# FPGA_IO.net
KiCad netlist of a schematic drawn in Altium Designer
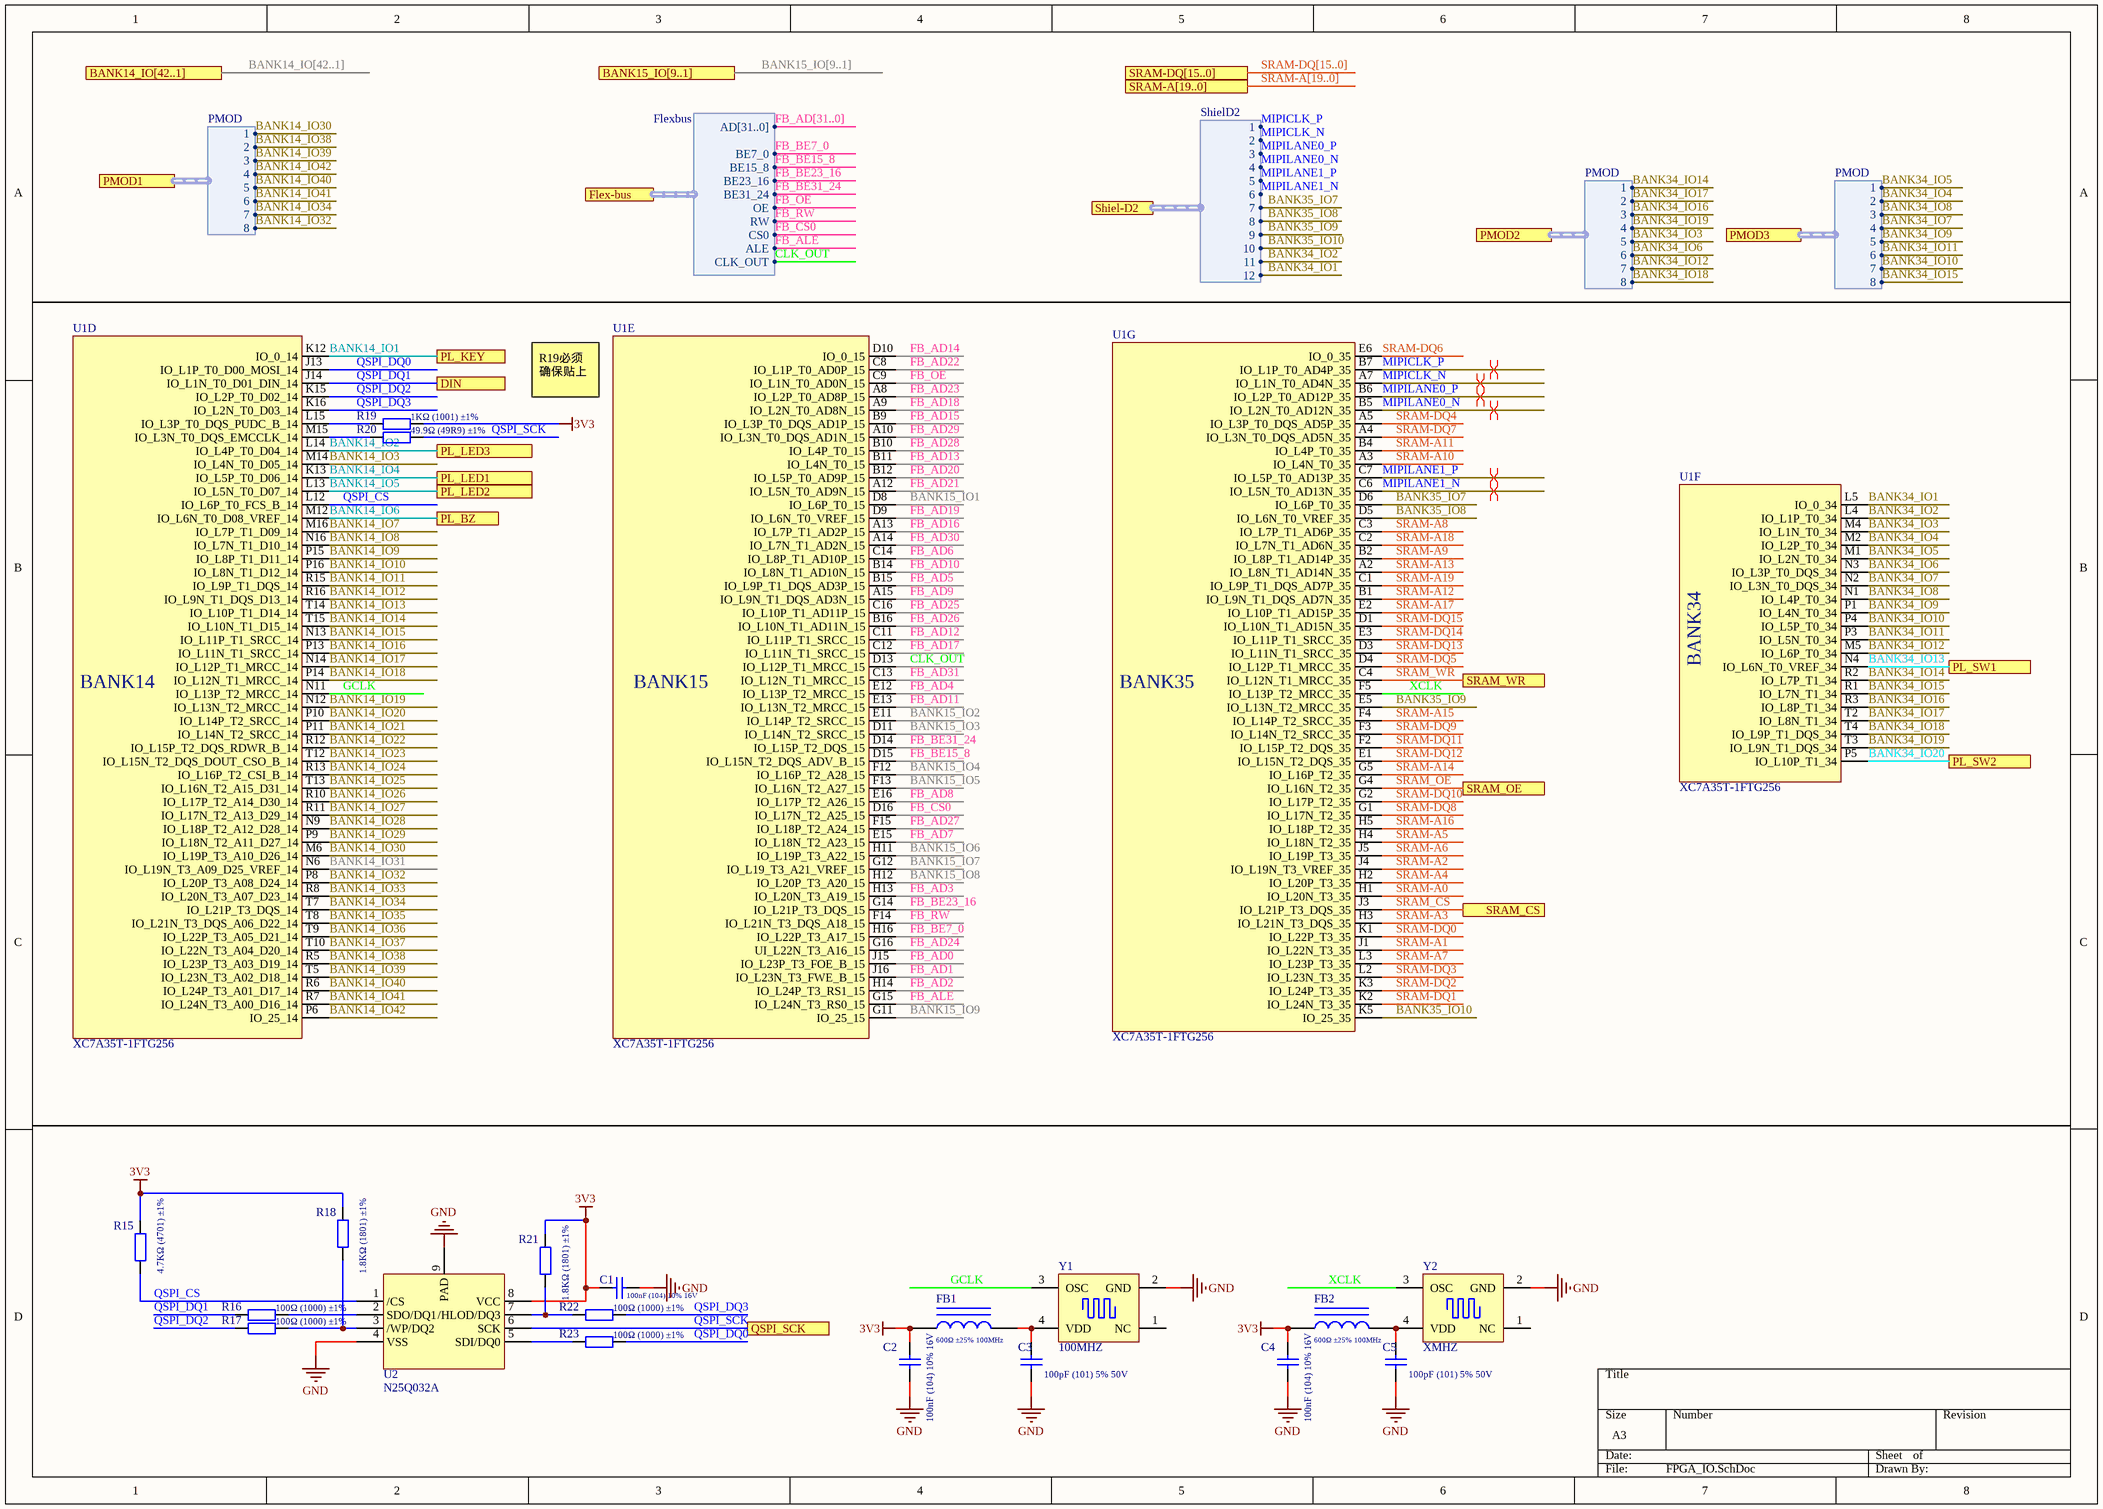
[diagram p0: FPGA_IO.SchDoc]

(export (version "E")
  (design (tool "Eeschema 10.0.6"))
  (components
    (comp (ref "C1")
      (value "100nF (104) 10% 16V")
      (footprint "0402_C")
      (description "贴片电容")
      (libsource (lib "Cap") (part "0402 100nF (104) 10% 16V"))
    )
    (comp (ref "C2")
      (value "100nF (104) 10% 16V")
      (footprint "0402_C")
      (description "贴片电容")
      (libsource (lib "Cap") (part "0402 100nF (104) 10% 16V"))
    )
    (comp (ref "C3")
      (value "100pF (101) 5% 50V")
      (footprint "0402_C")
      (description "贴片电容")
      (libsource (lib "Cap") (part "0402 100pF (101) 5% 50V"))
    )
    (comp (ref "C4")
      (value "100nF (104) 10% 16V")
      (footprint "0402_C")
      (description "贴片电容")
      (libsource (lib "Cap") (part "0402 100nF (104) 10% 16V"))
    )
    (comp (ref "C5")
      (value "100pF (101) 5% 50V")
      (footprint "0402_C")
      (description "贴片电容")
      (libsource (lib "Cap") (part "0402 100pF (101) 5% 50V"))
    )
    (comp (ref "FB1")
      (value "600Ω ±25% 100MHz")
      (footprint "0805_L")
      (description "贴片磁珠")
      (libsource (lib "IUD") (part "0805 600Ω 25% 100MHz"))
    )
    (comp (ref "FB2")
      (value "600Ω ±25% 100MHz")
      (footprint "0805_L")
      (description "贴片磁珠")
      (libsource (lib "IUD") (part "0805 600Ω 25% 100MHz"))
    )
    (comp (ref "R15")
      (value "4.7KΩ (4701) ±1%")
      (footprint "0402_R")
      (description "贴片电阻")
      (libsource (lib "RES") (part "0402 4.7KΩ (4701) 1%"))
    )
    (comp (ref "R16")
      (value "100Ω (1000) ±1%")
      (footprint "0402_R")
      (description "贴片电阻")
      (libsource (lib "RES") (part "0402 100Ω (1000) 1%"))
    )
    (comp (ref "R17")
      (value "100Ω (1000) ±1%")
      (footprint "0402_R")
      (description "贴片电阻")
      (libsource (lib "RES") (part "0402 100Ω (1000) 1%"))
    )
    (comp (ref "R18")
      (value "1.8KΩ (1801) ±1%")
      (footprint "0603_R")
      (description "贴片电阻")
      (libsource (lib "RES") (part "0603 1.8KΩ (1801) 1%"))
    )
    (comp (ref "R19")
      (value "1KΩ (1001) ±1%")
      (footprint "0402_R")
      (description "贴片电阻")
      (libsource (lib "RES") (part "0402 1KΩ (1001) 1%"))
    )
    (comp (ref "R20")
      (value "49.9Ω (49R9) ±1%")
      (footprint "0402_R")
      (description "贴片电阻")
      (libsource (lib "RES") (part "0402 49.9Ω (49R9) 1%"))
    )
    (comp (ref "R21")
      (value "1.8KΩ (1801) ±1%")
      (footprint "0603_R")
      (description "贴片电阻")
      (libsource (lib "RES") (part "0603 1.8KΩ (1801) 1%"))
    )
    (comp (ref "R22")
      (value "100Ω (1000) ±1%")
      (footprint "0402_R")
      (description "贴片电阻")
      (libsource (lib "RES") (part "0402 100Ω (1000) 1%"))
    )
    (comp (ref "R23")
      (value "100Ω (1000) ±1%")
      (footprint "0402_R")
      (description "贴片电阻")
      (libsource (lib "RES") (part "0402 100Ω (1000) 1%"))
    )
    (comp (ref "U1")
      (value "XC7A35T-1FTG256")
      (footprint "BGA100P9X9-81A")
      (libsource (lib "Schlib") (part "XC7A35T-1FTG256"))
    )
    (comp (ref "U2")
      (value "N25Q032A")
      (footprint "QFN127P500X600X100_HS-9N")
      (libsource (lib "2号库") (part "N25Q032A"))
    )
    (comp (ref "Y1") (value "100MHZ") (footprint "XTAL7_3225") (libsource (lib "K60-V4.0") (part "XTAL1")))
    (comp (ref "Y2") (value "XMHZ") (footprint "XTAL7_3225") (libsource (lib "K60-V4.0") (part "XTAL1")))
  )
  (nets
    (net (code "4") (name "/BANK14_IO1") (class "Default")
      (node (ref "U1") (pin "K12") (pinfunction "IO_0_14_K12") (pintype "passive"))
    )
    (net (code "5") (name "/BANK14_IO2") (class "Default")
      (node (ref "U1") (pin "L14") (pinfunction "IO_L4P_T0_D04_14_L14") (pintype "passive"))
    )
    (net (code "6") (name "/BANK14_IO3") (class "Default")
      (node (ref "U1") (pin "M14") (pinfunction "IO_L4N_T0_D05_14_M14") (pintype "passive"))
    )
    (net (code "7") (name "/BANK14_IO4") (class "Default")
      (node (ref "U1") (pin "K13") (pinfunction "IO_L5P_T0_D06_14_K13") (pintype "passive"))
    )
    (net (code "8") (name "/BANK14_IO5") (class "Default")
      (node (ref "U1") (pin "L13") (pinfunction "IO_L5N_T0_D07_14_L13") (pintype "passive"))
    )
    (net (code "9") (name "/BANK14_IO6") (class "Default")
      (node (ref "U1") (pin "M12") (pinfunction "IO_L6N_T0_D08_VREF_14_M12") (pintype "passive"))
    )
    (net (code "10") (name "/BANK14_IO7") (class "Default")
      (node (ref "U1") (pin "M16") (pinfunction "IO_L7P_T1_D09_14_M16") (pintype "passive"))
    )
    (net (code "11") (name "/BANK14_IO8") (class "Default")
      (node (ref "U1") (pin "N16") (pinfunction "IO_L7N_T1_D10_14_N16") (pintype "passive"))
    )
    (net (code "12") (name "/BANK14_IO9") (class "Default")
      (node (ref "U1") (pin "P15") (pinfunction "IO_L8P_T1_D11_14_P15") (pintype "passive"))
    )
    (net (code "13") (name "/BANK14_IO10") (class "Default")
      (node (ref "U1") (pin "P16") (pinfunction "IO_L8N_T1_D12_14_P16") (pintype "passive"))
    )
    (net (code "14") (name "/BANK14_IO11") (class "Default")
      (node (ref "U1") (pin "R15") (pinfunction "IO_L9P_T1_DQS_14_R15") (pintype "passive"))
    )
    (net (code "15") (name "/BANK14_IO12") (class "Default")
      (node (ref "U1") (pin "R16") (pinfunction "IO_L9N_T1_DQS_D13_14_R16") (pintype "passive"))
    )
    (net (code "16") (name "/BANK14_IO13") (class "Default")
      (node (ref "U1") (pin "T14") (pinfunction "IO_L10P_T1_D14_14_T14") (pintype "passive"))
    )
    (net (code "17") (name "/BANK14_IO14") (class "Default")
      (node (ref "U1") (pin "T15") (pinfunction "IO_L10N_T1_D15_14_T15") (pintype "passive"))
    )
    (net (code "18") (name "/BANK14_IO15") (class "Default")
      (node (ref "U1") (pin "N13") (pinfunction "IO_L11P_T1_SRCC_14_N13") (pintype "passive"))
    )
    (net (code "19") (name "/BANK14_IO16") (class "Default")
      (node (ref "U1") (pin "P13") (pinfunction "IO_L11N_T1_SRCC_14_P13") (pintype "passive"))
    )
    (net (code "20") (name "/BANK14_IO17") (class "Default")
      (node (ref "U1") (pin "N14") (pinfunction "IO_L12P_T1_MRCC_14_N14") (pintype "passive"))
    )
    (net (code "21") (name "/BANK14_IO18") (class "Default")
      (node (ref "U1") (pin "P14") (pinfunction "IO_L12N_T1_MRCC_14_P14") (pintype "passive"))
    )
    (net (code "22") (name "/BANK14_IO19") (class "Default")
      (node (ref "U1") (pin "N12") (pinfunction "IO_L13N_T2_MRCC_14_N12") (pintype "passive"))
    )
    (net (code "23") (name "/BANK14_IO20") (class "Default")
      (node (ref "U1") (pin "P10") (pinfunction "IO_L14P_T2_SRCC_14_P10") (pintype "passive"))
    )
    (net (code "24") (name "/BANK14_IO21") (class "Default")
      (node (ref "U1") (pin "P11") (pinfunction "IO_L14N_T2_SRCC_14_P11") (pintype "passive"))
    )
    (net (code "25") (name "/BANK14_IO22") (class "Default")
      (node (ref "U1") (pin "R12") (pinfunction "IO_L15P_T2_DQS_RDWR_B_14_R12") (pintype "passive"))
    )
    (net (code "26") (name "/BANK14_IO23") (class "Default")
      (node (ref "U1") (pin "T12") (pinfunction "IO_L15N_T2_DQS_DOUT_CSO_B_14_T12") (pintype "passive"))
    )
    (net (code "27") (name "/BANK14_IO24") (class "Default")
      (node (ref "U1") (pin "R13") (pinfunction "IO_L16P_T2_CSI_B_14_R13") (pintype "passive"))
    )
    (net (code "28") (name "/BANK14_IO25") (class "Default")
      (node (ref "U1") (pin "T13") (pinfunction "IO_L16N_T2_A15_D31_14_T13") (pintype "passive"))
    )
    (net (code "29") (name "/BANK14_IO26") (class "Default")
      (node (ref "U1") (pin "R10") (pinfunction "IO_L17P_T2_A14_D30_14_R10") (pintype "passive"))
    )
    (net (code "30") (name "/BANK14_IO27") (class "Default")
      (node (ref "U1") (pin "R11") (pinfunction "IO_L17N_T2_A13_D29_14_R11") (pintype "passive"))
    )
    (net (code "31") (name "/BANK14_IO28") (class "Default")
      (node (ref "U1") (pin "N9") (pinfunction "IO_L18P_T2_A12_D28_14_N9") (pintype "passive"))
    )
    (net (code "32") (name "/BANK14_IO29") (class "Default")
      (node (ref "U1") (pin "P9") (pinfunction "IO_L18N_T2_A11_D27_14_P9") (pintype "passive"))
    )
    (net (code "33") (name "/BANK14_IO30") (class "Default")
      (node (ref "U1") (pin "M6") (pinfunction "IO_L19P_T3_A10_D26_14_M6") (pintype "passive"))
    )
    (net (code "34") (name "/BANK14_IO31") (class "Default")
      (node (ref "U1") (pin "N6") (pinfunction "IO_L19N_T3_A09_D25_VREF_14_N6") (pintype "passive"))
    )
    (net (code "35") (name "/BANK14_IO32") (class "Default")
      (node (ref "U1") (pin "P8") (pinfunction "IO_L20P_T3_A08_D24_14_P8") (pintype "passive"))
    )
    (net (code "36") (name "/BANK14_IO33") (class "Default")
      (node (ref "U1") (pin "R8") (pinfunction "IO_L20N_T3_A07_D23_14_R8") (pintype "passive"))
    )
    (net (code "37") (name "/BANK14_IO34") (class "Default")
      (node (ref "U1") (pin "T7") (pinfunction "IO_L21P_T3_DQS_14_T7") (pintype "passive"))
    )
    (net (code "38") (name "/BANK14_IO35") (class "Default")
      (node (ref "U1") (pin "T8") (pinfunction "IO_L21N_T3_DQS_A06_D22_14_T8") (pintype "passive"))
    )
    (net (code "39") (name "/BANK14_IO36") (class "Default")
      (node (ref "U1") (pin "T9") (pinfunction "IO_L22P_T3_A05_D21_14_T9") (pintype "passive"))
    )
    (net (code "40") (name "/BANK14_IO37") (class "Default")
      (node (ref "U1") (pin "T10") (pinfunction "IO_L22N_T3_A04_D20_14_T10") (pintype "passive"))
    )
    (net (code "41") (name "/BANK14_IO38") (class "Default")
      (node (ref "U1") (pin "R5") (pinfunction "IO_L23P_T3_A03_D19_14_R5") (pintype "passive"))
    )
    (net (code "42") (name "/BANK14_IO39") (class "Default")
      (node (ref "U1") (pin "T5") (pinfunction "IO_L23N_T3_A02_D18_14_T5") (pintype "passive"))
    )
    (net (code "43") (name "/BANK14_IO40") (class "Default")
      (node (ref "U1") (pin "R6") (pinfunction "IO_L24P_T3_A01_D17_14_R6") (pintype "passive"))
    )
    (net (code "44") (name "/BANK14_IO41") (class "Default")
      (node (ref "U1") (pin "R7") (pinfunction "IO_L24N_T3_A00_D16_14_R7") (pintype "passive"))
    )
    (net (code "45") (name "/BANK14_IO42") (class "Default")
      (node (ref "U1") (pin "P6") (pinfunction "IO_25_14_P6") (pintype "passive"))
    )
    (net (code "47") (name "/BANK15_IO1") (class "Default")
      (node (ref "U1") (pin "D8") (pinfunction "IO_L6P_T0_15_D8") (pintype "passive"))
    )
    (net (code "48") (name "/BANK15_IO2") (class "Default")
      (node (ref "U1") (pin "E11") (pinfunction "IO_L14P_T2_SRCC_15_E11") (pintype "passive"))
    )
    (net (code "49") (name "/BANK15_IO3") (class "Default")
      (node (ref "U1") (pin "D11") (pinfunction "IO_L14N_T2_SRCC_15_D11") (pintype "passive"))
    )
    (net (code "50") (name "/BANK15_IO4") (class "Default")
      (node (ref "U1") (pin "F12") (pinfunction "IO_L16P_T2_A28_15_F12") (pintype "passive"))
    )
    (net (code "51") (name "/BANK15_IO5") (class "Default")
      (node (ref "U1") (pin "F13") (pinfunction "IO_L16N_T2_A27_15_F13") (pintype "passive"))
    )
    (net (code "52") (name "/BANK15_IO6") (class "Default")
      (node (ref "U1") (pin "H11") (pinfunction "IO_L19P_T3_A22_15_H11") (pintype "passive"))
    )
    (net (code "53") (name "/BANK15_IO7") (class "Default")
      (node (ref "U1") (pin "G12") (pinfunction "IO_L19_T3_A21_VREF_15_G12") (pintype "passive"))
    )
    (net (code "54") (name "/BANK15_IO8") (class "Default")
      (node (ref "U1") (pin "H12") (pinfunction "IO_L20P_T3_A20_15_H12") (pintype "passive"))
    )
    (net (code "55") (name "/BANK15_IO9") (class "Default")
      (node (ref "U1") (pin "G11") (pinfunction "IO_25_15_G11") (pintype "passive"))
    )
    (net (code "57") (name "/BANK34_IO1") (class "Default")
      (node (ref "U1") (pin "L5") (pinfunction "IO_0_34_L5") (pintype "passive"))
    )
    (net (code "58") (name "/BANK34_IO2") (class "Default")
      (node (ref "U1") (pin "L4") (pinfunction "IO_L1P_T0_34_L4") (pintype "passive"))
    )
    (net (code "59") (name "/BANK34_IO3") (class "Default")
      (node (ref "U1") (pin "M4") (pinfunction "IO_L1N_T0_34_M4") (pintype "passive"))
    )
    (net (code "60") (name "/BANK34_IO4") (class "Default")
      (node (ref "U1") (pin "M2") (pinfunction "IO_L2P_T0_34_M2") (pintype "passive"))
    )
    (net (code "61") (name "/BANK34_IO5") (class "Default")
      (node (ref "U1") (pin "M1") (pinfunction "IO_L2N_T0_34_M1") (pintype "passive"))
    )
    (net (code "62") (name "/BANK34_IO6") (class "Default")
      (node (ref "U1") (pin "N3") (pinfunction "IO_L3P_T0_DQS_34_N3") (pintype "passive"))
    )
    (net (code "63") (name "/BANK34_IO7") (class "Default")
      (node (ref "U1") (pin "N2") (pinfunction "IO_L3N_T0_DQS_34_N2") (pintype "passive"))
    )
    (net (code "64") (name "/BANK34_IO8") (class "Default")
      (node (ref "U1") (pin "N1") (pinfunction "IO_L4P_T0_34_N1") (pintype "passive"))
    )
    (net (code "65") (name "/BANK34_IO9") (class "Default")
      (node (ref "U1") (pin "P1") (pinfunction "IO_L4N_T0_34_P1") (pintype "passive"))
    )
    (net (code "66") (name "/BANK34_IO10") (class "Default")
      (node (ref "U1") (pin "P4") (pinfunction "IO_L5P_T0_34_P4") (pintype "passive"))
    )
    (net (code "67") (name "/BANK34_IO11") (class "Default")
      (node (ref "U1") (pin "P3") (pinfunction "IO_L5N_T0_34_P3") (pintype "passive"))
    )
    (net (code "68") (name "/BANK34_IO12") (class "Default")
      (node (ref "U1") (pin "M5") (pinfunction "IO_L6P_T0_34_M5") (pintype "passive"))
    )
    (net (code "69") (name "/BANK34_IO13") (class "Default")
      (node (ref "U1") (pin "N4") (pinfunction "IO_L6N_T0_VREF_34_N4") (pintype "passive"))
    )
    (net (code "70") (name "/BANK34_IO14") (class "Default")
      (node (ref "U1") (pin "R2") (pinfunction "IO_L7P_T1_34_R2") (pintype "passive"))
    )
    (net (code "71") (name "/BANK34_IO15") (class "Default")
      (node (ref "U1") (pin "R1") (pinfunction "IO_L7N_T1_34_R1") (pintype "passive"))
    )
    (net (code "72") (name "/BANK34_IO16") (class "Default")
      (node (ref "U1") (pin "R3") (pinfunction "IO_L8P_T1_34_R3") (pintype "passive"))
    )
    (net (code "73") (name "/BANK34_IO17") (class "Default")
      (node (ref "U1") (pin "T2") (pinfunction "IO_L8N_T1_34_T2") (pintype "passive"))
    )
    (net (code "74") (name "/BANK34_IO18") (class "Default")
      (node (ref "U1") (pin "T4") (pinfunction "IO_L9P_T1_DQS_34_T4") (pintype "passive"))
    )
    (net (code "75") (name "/BANK34_IO19") (class "Default")
      (node (ref "U1") (pin "T3") (pinfunction "IO_L9N_T1_DQS_34_T3") (pintype "passive"))
    )
    (net (code "76") (name "/BANK34_IO20") (class "Default")
      (node (ref "U1") (pin "P5") (pinfunction "IO_L10P_T1_34_P5") (pintype "passive"))
    )
    (net (code "77") (name "/BANK35_IO7") (class "Default")
      (node (ref "U1") (pin "D6") (pinfunction "IO_L6P_T0_35_D6") (pintype "passive"))
    )
    (net (code "78") (name "/BANK35_IO8") (class "Default")
      (node (ref "U1") (pin "D5") (pinfunction "IO_L6N_T0_VREF_35_D5") (pintype "passive"))
    )
    (net (code "79") (name "/BANK35_IO9") (class "Default")
      (node (ref "U1") (pin "E5") (pinfunction "IO_L13N_T2_MRCC_35_E5") (pintype "passive"))
    )
    (net (code "80") (name "/BANK35_IO10") (class "Default")
      (node (ref "U1") (pin "K5") (pinfunction "IO_25_35_K5") (pintype "passive"))
    )
    (net (code "81") (name "/CLK_OUT") (class "Default")
      (node (ref "U1") (pin "D13") (pinfunction "IO_L12P_T1_MRCC_15_D13") (pintype "passive"))
    )
    (net (code "82") (name "/FB_AD0") (class "Default")
      (node (ref "U1") (pin "J15") (pinfunction "IO_L23P_T3_FOE_B_15_J15") (pintype "passive"))
    )
    (net (code "83") (name "/FB_AD1") (class "Default")
      (node (ref "U1") (pin "J16") (pinfunction "IO_L23N_T3_FWE_B_15_J16") (pintype "passive"))
    )
    (net (code "84") (name "/FB_AD2") (class "Default")
      (node (ref "U1") (pin "H14") (pinfunction "IO_L24P_T3_RS1_15_H14") (pintype "passive"))
    )
    (net (code "85") (name "/FB_AD3") (class "Default")
      (node (ref "U1") (pin "H13") (pinfunction "IO_L20N_T3_A19_15_H13") (pintype "passive"))
    )
    (net (code "86") (name "/FB_AD4") (class "Default")
      (node (ref "U1") (pin "E12") (pinfunction "IO_L13P_T2_MRCC_15_E12") (pintype "passive"))
    )
    (net (code "87") (name "/FB_AD5") (class "Default")
      (node (ref "U1") (pin "B15") (pinfunction "IO_L9P_T1_DQS_AD3P_15_B15") (pintype "passive"))
    )
    (net (code "88") (name "/FB_AD6") (class "Default")
      (node (ref "U1") (pin "C14") (pinfunction "IO_L8P_T1_AD10P_15_C14") (pintype "passive"))
    )
    (net (code "89") (name "/FB_AD7") (class "Default")
      (node (ref "U1") (pin "E15") (pinfunction "IO_L18N_T2_A23_15_E15") (pintype "passive"))
    )
    (net (code "90") (name "/FB_AD8") (class "Default")
      (node (ref "U1") (pin "E16") (pinfunction "IO_L17P_T2_A26_15_E16") (pintype "passive"))
    )
    (net (code "91") (name "/FB_AD9") (class "Default")
      (node (ref "U1") (pin "A15") (pinfunction "IO_L9N_T1_DQS_AD3N_15_A15") (pintype "passive"))
    )
    (net (code "92") (name "/FB_AD10") (class "Default")
      (node (ref "U1") (pin "B14") (pinfunction "IO_L8N_T1_AD10N_15_B14") (pintype "passive"))
    )
    (net (code "93") (name "/FB_AD11") (class "Default")
      (node (ref "U1") (pin "E13") (pinfunction "IO_L13N_T2_MRCC_15_E13") (pintype "passive"))
    )
    (net (code "94") (name "/FB_AD12") (class "Default")
      (node (ref "U1") (pin "C11") (pinfunction "IO_L11P_T1_SRCC_15_C11") (pintype "passive"))
    )
    (net (code "95") (name "/FB_AD13") (class "Default")
      (node (ref "U1") (pin "B11") (pinfunction "IO_L4N_T0_15_B11") (pintype "passive"))
    )
    (net (code "96") (name "/FB_AD14") (class "Default")
      (node (ref "U1") (pin "D10") (pinfunction "IO_0_15_D10") (pintype "passive"))
    )
    (net (code "97") (name "/FB_AD15") (class "Default")
      (node (ref "U1") (pin "B9") (pinfunction "IO_L3P_T0_DQS_AD1P_15_B9") (pintype "passive"))
    )
    (net (code "98") (name "/FB_AD16") (class "Default")
      (node (ref "U1") (pin "A13") (pinfunction "IO_L7P_T1_AD2P_15_A13") (pintype "passive"))
    )
    (net (code "99") (name "/FB_AD17") (class "Default")
      (node (ref "U1") (pin "C12") (pinfunction "IO_L11N_T1_SRCC_15_C12") (pintype "passive"))
    )
    (net (code "100") (name "/FB_AD18") (class "Default")
      (node (ref "U1") (pin "A9") (pinfunction "IO_L2N_T0_AD8N_15_A9") (pintype "passive"))
    )
    (net (code "101") (name "/FB_AD19") (class "Default")
      (node (ref "U1") (pin "D9") (pinfunction "IO_L6N_T0_VREF_15_D9") (pintype "passive"))
    )
    (net (code "102") (name "/FB_AD20") (class "Default")
      (node (ref "U1") (pin "B12") (pinfunction "IO_L5P_T0_AD9P_15_B12") (pintype "passive"))
    )
    (net (code "103") (name "/FB_AD21") (class "Default")
      (node (ref "U1") (pin "A12") (pinfunction "IO_L5N_T0_AD9N_15_A12") (pintype "passive"))
    )
    (net (code "104") (name "/FB_AD22") (class "Default")
      (node (ref "U1") (pin "C8") (pinfunction "IO_L1P_T0_AD0P_15_C8") (pintype "passive"))
    )
    (net (code "105") (name "/FB_AD23") (class "Default")
      (node (ref "U1") (pin "A8") (pinfunction "IO_L2P_T0_AD8P_15_A8") (pintype "passive"))
    )
    (net (code "106") (name "/FB_AD24") (class "Default")
      (node (ref "U1") (pin "G16") (pinfunction "UI_L22N_T3_A16_15_G16") (pintype "passive"))
    )
    (net (code "107") (name "/FB_AD25") (class "Default")
      (node (ref "U1") (pin "C16") (pinfunction "IO_L10P_T1_AD11P_15_C16") (pintype "passive"))
    )
    (net (code "108") (name "/FB_AD26") (class "Default")
      (node (ref "U1") (pin "B16") (pinfunction "IO_L10N_T1_AD11N_15_B16") (pintype "passive"))
    )
    (net (code "109") (name "/FB_AD27") (class "Default")
      (node (ref "U1") (pin "F15") (pinfunction "IO_L18P_T2_A24_15_F15") (pintype "passive"))
    )
    (net (code "110") (name "/FB_AD28") (class "Default")
      (node (ref "U1") (pin "B10") (pinfunction "IO_L4P_T0_15_B10") (pintype "passive"))
    )
    (net (code "111") (name "/FB_AD29") (class "Default")
      (node (ref "U1") (pin "A10") (pinfunction "IO_L3N_T0_DQS_AD1N_15_A10") (pintype "passive"))
    )
    (net (code "112") (name "/FB_AD30") (class "Default")
      (node (ref "U1") (pin "A14") (pinfunction "IO_L7N_T1_AD2N_15_A14") (pintype "passive"))
    )
    (net (code "113") (name "/FB_AD31") (class "Default")
      (node (ref "U1") (pin "C13") (pinfunction "IO_L12N_T1_MRCC_15_C13") (pintype "passive"))
    )
    (net (code "114") (name "/FB_ALE") (class "Default")
      (node (ref "U1") (pin "G15") (pinfunction "IO_L24N_T3_RS0_15_G15") (pintype "passive"))
    )
    (net (code "115") (name "/FB_BE7_0") (class "Default")
      (node (ref "U1") (pin "H16") (pinfunction "IO_L22P_T3_A17_15_H16") (pintype "passive"))
    )
    (net (code "116") (name "/FB_BE15_8") (class "Default")
      (node (ref "U1") (pin "D15") (pinfunction "IO_L15N_T2_DQS_ADV_B_15_D15") (pintype "passive"))
    )
    (net (code "117") (name "/FB_BE23_16") (class "Default")
      (node (ref "U1") (pin "G14") (pinfunction "IO_L21P_T3_DQS_15_G14") (pintype "passive"))
    )
    (net (code "118") (name "/FB_BE31_24") (class "Default")
      (node (ref "U1") (pin "D14") (pinfunction "IO_L15P_T2_DQS_15_D14") (pintype "passive"))
    )
    (net (code "119") (name "/FB_CS0") (class "Default")
      (node (ref "U1") (pin "D16") (pinfunction "IO_L17N_T2_A25_15_D16") (pintype "passive"))
    )
    (net (code "120") (name "/FB_OE") (class "Default")
      (node (ref "U1") (pin "C9") (pinfunction "IO_L1N_T0_AD0N_15_C9") (pintype "passive"))
    )
    (net (code "121") (name "/FB_RW") (class "Default")
      (node (ref "U1") (pin "F14") (pinfunction "IO_L21N_T3_DQS_A18_15_F14") (pintype "passive"))
    )
    (net (code "123") (name "/GCLK") (class "Default")
      (node (ref "U1") (pin "N11") (pinfunction "IO_L13P_T2_MRCC_14_N11") (pintype "passive"))
      (node (ref "Y1") (pin "3") (pinfunction "OSC_3") (pintype "passive"))
    )
    (net (code "124") (name "/MIPICLK_N") (class "Default")
      (node (ref "U1") (pin "A7") (pinfunction "IO_L1N_T0_AD4N_35_A7") (pintype "passive"))
    )
    (net (code "125") (name "/MIPICLK_P") (class "Default")
      (node (ref "U1") (pin "B7") (pinfunction "IO_L1P_T0_AD4P_35_B7") (pintype "passive"))
    )
    (net (code "126") (name "/MIPILANE0_N") (class "Default")
      (node (ref "U1") (pin "B5") (pinfunction "IO_L2N_T0_AD12N_35_B5") (pintype "passive"))
    )
    (net (code "127") (name "/MIPILANE0_P") (class "Default")
      (node (ref "U1") (pin "B6") (pinfunction "IO_L2P_T0_AD12P_35_B6") (pintype "passive"))
    )
    (net (code "128") (name "/MIPILANE1_N") (class "Default")
      (node (ref "U1") (pin "C6") (pinfunction "IO_L5N_T0_AD13N_35_C6") (pintype "passive"))
    )
    (net (code "129") (name "/MIPILANE1_P") (class "Default")
      (node (ref "U1") (pin "C7") (pinfunction "IO_L5P_T0_AD13P_35_C7") (pintype "passive"))
    )
    (net (code "130") (name "/QSPI_CS") (class "Default")
      (node (ref "R15") (pin "1") (pinfunction "1_1") (pintype "passive"))
      (node (ref "U1") (pin "L12") (pinfunction "IO_L6P_T0_FCS_B_14_L12") (pintype "passive"))
      (node (ref "U2") (pin "1") (pinfunction "/CS_1") (pintype "passive"))
    )
    (net (code "131") (name "/QSPI_DQ0") (class "Default")
      (node (ref "R23") (pin "2") (pinfunction "2_2") (pintype "passive"))
      (node (ref "U1") (pin "J13") (pinfunction "IO_L1P_T0_D00_MOSI_14_J13") (pintype "passive"))
    )
    (net (code "132") (name "/QSPI_DQ1") (class "Default")
      (node (ref "R16") (pin "1") (pinfunction "1_1") (pintype "passive"))
      (node (ref "U1") (pin "J14") (pinfunction "IO_L1N_T0_D01_DIN_14_J14") (pintype "passive"))
    )
    (net (code "133") (name "/QSPI_DQ2") (class "Default")
      (node (ref "R17") (pin "1") (pinfunction "1_1") (pintype "passive"))
      (node (ref "U1") (pin "K15") (pinfunction "IO_L2P_T0_D02_14_K15") (pintype "passive"))
    )
    (net (code "134") (name "/QSPI_DQ3") (class "Default")
      (node (ref "R22") (pin "2") (pinfunction "2_2") (pintype "passive"))
      (node (ref "U1") (pin "K16") (pinfunction "IO_L2N_T0_D03_14_K16") (pintype "passive"))
    )
    (net (code "135") (name "/QSPI_SCK") (class "Default")
      (node (ref "R20") (pin "2") (pinfunction "2_2") (pintype "passive"))
      (node (ref "U2") (pin "6") (pinfunction "SCK_6") (pintype "passive"))
    )
    (net (code "136") (name "/SRAM-A0") (class "Default")
      (node (ref "U1") (pin "H1") (pinfunction "IO_L20N_T3_35_H1") (pintype "passive"))
    )
    (net (code "137") (name "/SRAM-A1") (class "Default")
      (node (ref "U1") (pin "J1") (pinfunction "IO_L22N_T3_35_J1") (pintype "passive"))
    )
    (net (code "138") (name "/SRAM-A2") (class "Default")
      (node (ref "U1") (pin "J4") (pinfunction "IO_L19N_T3_VREF_35_J4") (pintype "passive"))
    )
    (net (code "139") (name "/SRAM-A3") (class "Default")
      (node (ref "U1") (pin "H3") (pinfunction "IO_L21N_T3_DQS_35_H3") (pintype "passive"))
    )
    (net (code "140") (name "/SRAM-A4") (class "Default")
      (node (ref "U1") (pin "H2") (pinfunction "IO_L20P_T3_35_H2") (pintype "passive"))
    )
    (net (code "141") (name "/SRAM-A5") (class "Default")
      (node (ref "U1") (pin "H4") (pinfunction "IO_L18N_T2_35_H4") (pintype "passive"))
    )
    (net (code "142") (name "/SRAM-A6") (class "Default")
      (node (ref "U1") (pin "J5") (pinfunction "IO_L19P_T3_35_J5") (pintype "passive"))
    )
    (net (code "143") (name "/SRAM-A7") (class "Default")
      (node (ref "U1") (pin "L3") (pinfunction "IO_L23P_T3_35_L3") (pintype "passive"))
    )
    (net (code "144") (name "/SRAM-A8") (class "Default")
      (node (ref "U1") (pin "C3") (pinfunction "IO_L7P_T1_AD6P_35_C3") (pintype "passive"))
    )
    (net (code "145") (name "/SRAM-A9") (class "Default")
      (node (ref "U1") (pin "B2") (pinfunction "IO_L8P_T1_AD14P_35_B2") (pintype "passive"))
    )
    (net (code "146") (name "/SRAM-A10") (class "Default")
      (node (ref "U1") (pin "A3") (pinfunction "IO_L4N_T0_35_A3") (pintype "passive"))
    )
    (net (code "147") (name "/SRAM-A11") (class "Default")
      (node (ref "U1") (pin "B4") (pinfunction "IO_L4P_T0_35_B4") (pintype "passive"))
    )
    (net (code "148") (name "/SRAM-A12") (class "Default")
      (node (ref "U1") (pin "B1") (pinfunction "IO_L9N_T1_DQS_AD7N_35_B1") (pintype "passive"))
    )
    (net (code "149") (name "/SRAM-A13") (class "Default")
      (node (ref "U1") (pin "A2") (pinfunction "IO_L8N_T1_AD14N_35_A2") (pintype "passive"))
    )
    (net (code "150") (name "/SRAM-A14") (class "Default")
      (node (ref "U1") (pin "G5") (pinfunction "IO_L16P_T2_35_G5") (pintype "passive"))
    )
    (net (code "151") (name "/SRAM-A15") (class "Default")
      (node (ref "U1") (pin "F4") (pinfunction "IO_L14P_T2_SRCC_35_F4") (pintype "passive"))
    )
    (net (code "152") (name "/SRAM-A16") (class "Default")
      (node (ref "U1") (pin "H5") (pinfunction "IO_L18P_T2_35_H5") (pintype "passive"))
    )
    (net (code "153") (name "/SRAM-A17") (class "Default")
      (node (ref "U1") (pin "E2") (pinfunction "IO_L10P_T1_AD15P_35_E2") (pintype "passive"))
    )
    (net (code "154") (name "/SRAM-A18") (class "Default")
      (node (ref "U1") (pin "C2") (pinfunction "IO_L7N_T1_AD6N_35_C2") (pintype "passive"))
    )
    (net (code "155") (name "/SRAM-A19") (class "Default")
      (node (ref "U1") (pin "C1") (pinfunction "IO_L9P_T1_DQS_AD7P_35_C1") (pintype "passive"))
    )
    (net (code "157") (name "/SRAM-DQ0") (class "Default")
      (node (ref "U1") (pin "K1") (pinfunction "IO_L22P_T3_35_K1") (pintype "passive"))
    )
    (net (code "158") (name "/SRAM-DQ1") (class "Default")
      (node (ref "U1") (pin "K2") (pinfunction "IO_L24N_T3_35_K2") (pintype "passive"))
    )
    (net (code "159") (name "/SRAM-DQ2") (class "Default")
      (node (ref "U1") (pin "K3") (pinfunction "IO_L24P_T3_35_K3") (pintype "passive"))
    )
    (net (code "160") (name "/SRAM-DQ3") (class "Default")
      (node (ref "U1") (pin "L2") (pinfunction "IO_L23N_T3_35_L2") (pintype "passive"))
    )
    (net (code "161") (name "/SRAM-DQ4") (class "Default")
      (node (ref "U1") (pin "A5") (pinfunction "IO_L3P_T0_DQS_AD5P_35_A5") (pintype "passive"))
    )
    (net (code "162") (name "/SRAM-DQ5") (class "Default")
      (node (ref "U1") (pin "D4") (pinfunction "IO_L12P_T1_MRCC_35_D4") (pintype "passive"))
    )
    (net (code "163") (name "/SRAM-DQ6") (class "Default")
      (node (ref "U1") (pin "E6") (pinfunction "IO_0_35_E6") (pintype "passive"))
    )
    (net (code "164") (name "/SRAM-DQ7") (class "Default")
      (node (ref "U1") (pin "A4") (pinfunction "IO_L3N_T0_DQS_AD5N_35_A4") (pintype "passive"))
    )
    (net (code "165") (name "/SRAM-DQ8") (class "Default")
      (node (ref "U1") (pin "G1") (pinfunction "IO_L17N_T2_35_G1") (pintype "passive"))
    )
    (net (code "166") (name "/SRAM-DQ9") (class "Default")
      (node (ref "U1") (pin "F3") (pinfunction "IO_L14N_T2_SRCC_35_F3") (pintype "passive"))
    )
    (net (code "167") (name "/SRAM-DQ10") (class "Default")
      (node (ref "U1") (pin "G2") (pinfunction "IO_L17P_T2_35_G2") (pintype "passive"))
    )
    (net (code "168") (name "/SRAM-DQ11") (class "Default")
      (node (ref "U1") (pin "F2") (pinfunction "IO_L15P_T2_DQS_35_F2") (pintype "passive"))
    )
    (net (code "169") (name "/SRAM-DQ12") (class "Default")
      (node (ref "U1") (pin "E1") (pinfunction "IO_L15N_T2_DQS_35_E1") (pintype "passive"))
    )
    (net (code "170") (name "/SRAM-DQ13") (class "Default")
      (node (ref "U1") (pin "D3") (pinfunction "IO_L11N_T1_SRCC_35_D3") (pintype "passive"))
    )
    (net (code "171") (name "/SRAM-DQ14") (class "Default")
      (node (ref "U1") (pin "E3") (pinfunction "IO_L11P_T1_SRCC_35_E3") (pintype "passive"))
    )
    (net (code "172") (name "/SRAM-DQ15") (class "Default")
      (node (ref "U1") (pin "D1") (pinfunction "IO_L10N_T1_AD15N_35_D1") (pintype "passive"))
    )
    (net (code "174") (name "/SRAM_CS") (class "Default")
      (node (ref "U1") (pin "J3") (pinfunction "IO_L21P_T3_DQS_35_J3") (pintype "passive"))
    )
    (net (code "175") (name "/SRAM_OE") (class "Default")
      (node (ref "U1") (pin "G4") (pinfunction "IO_L16N_T2_35_G4") (pintype "passive"))
    )
    (net (code "176") (name "/SRAM_WR") (class "Default")
      (node (ref "U1") (pin "C4") (pinfunction "IO_L12N_T1_MRCC_35_C4") (pintype "passive"))
    )
    (net (code "177") (name "/XCLK") (class "Default")
      (node (ref "U1") (pin "F5") (pinfunction "IO_L13P_T2_MRCC_35_F5") (pintype "passive"))
      (node (ref "Y2") (pin "3") (pinfunction "OSC_3") (pintype "passive"))
    )
    (net (code "181") (name "3V3") (class "Default")
      (node (ref "C1") (pin "1") (pinfunction "1_1") (pintype "passive"))
      (node (ref "C2") (pin "2") (pinfunction "2_2") (pintype "passive"))
      (node (ref "C4") (pin "2") (pinfunction "2_2") (pintype "passive"))
      (node (ref "FB1") (pin "1") (pinfunction "1_1") (pintype "passive"))
      (node (ref "FB2") (pin "1") (pinfunction "1_1") (pintype "passive"))
      (node (ref "R15") (pin "2") (pinfunction "2_2") (pintype "passive"))
      (node (ref "R18") (pin "2") (pinfunction "2_2") (pintype "passive"))
      (node (ref "R19") (pin "2") (pinfunction "2_2") (pintype "passive"))
      (node (ref "R21") (pin "2") (pinfunction "2_2") (pintype "passive"))
      (node (ref "U2") (pin "8") (pinfunction "VCC_8") (pintype "passive"))
    )
    (net (code "182") (name "GND") (class "Default")
      (node (ref "C1") (pin "2") (pinfunction "2_2") (pintype "passive"))
      (node (ref "C2") (pin "1") (pinfunction "1_1") (pintype "passive"))
      (node (ref "C3") (pin "1") (pinfunction "1_1") (pintype "passive"))
      (node (ref "C4") (pin "1") (pinfunction "1_1") (pintype "passive"))
      (node (ref "C5") (pin "1") (pinfunction "1_1") (pintype "passive"))
      (node (ref "U2") (pin "4") (pinfunction "VSS_4") (pintype "passive"))
      (node (ref "U2") (pin "9") (pinfunction "PAD_9") (pintype "passive"))
      (node (ref "Y1") (pin "2") (pinfunction "GND_2") (pintype "passive"))
      (node (ref "Y2") (pin "2") (pinfunction "GND_2") (pintype "passive"))
    )
    (net (code "183") (name "Net-(U1D-IO_L3N_T0_DQS_EMCCLK_14)") (class "Default")
      (node (ref "R20") (pin "1") (pinfunction "1_1") (pintype "passive"))
      (node (ref "U1") (pin "M15") (pinfunction "IO_L3N_T0_DQS_EMCCLK_14_M15") (pintype "passive"))
    )
    (net (code "184") (name "Net-(U1D-IO_L3P_T0_DQS_PUDC_B_14)") (class "Default")
      (node (ref "R19") (pin "1") (pinfunction "1_1") (pintype "passive"))
      (node (ref "U1") (pin "L15") (pinfunction "IO_L3P_T0_DQS_PUDC_B_14_L15") (pintype "passive"))
    )
    (net (code "185") (name "Net-(U2-SDI{slash}DQ0)") (class "Default")
      (node (ref "R23") (pin "1") (pinfunction "1_1") (pintype "passive"))
      (node (ref "U2") (pin "5") (pinfunction "SDI/DQ0_5") (pintype "passive"))
    )
    (net (code "186") (name "Net-(U2-SDO{slash}DQ1)") (class "Default")
      (node (ref "R16") (pin "2") (pinfunction "2_2") (pintype "passive"))
      (node (ref "U2") (pin "2") (pinfunction "SDO/DQ1_2") (pintype "passive"))
    )
    (net (code "187") (name "Net-(U2-{slash}HLOD{slash}DQ3)") (class "Default")
      (node (ref "R21") (pin "1") (pinfunction "1_1") (pintype "passive"))
      (node (ref "R22") (pin "1") (pinfunction "1_1") (pintype "passive"))
      (node (ref "U2") (pin "7") (pinfunction "/HLOD/DQ3_7") (pintype "passive"))
    )
    (net (code "188") (name "Net-(U2-{slash}WP{slash}DQ2)") (class "Default")
      (node (ref "R17") (pin "2") (pinfunction "2_2") (pintype "passive"))
      (node (ref "R18") (pin "1") (pinfunction "1_1") (pintype "passive"))
      (node (ref "U2") (pin "3") (pinfunction "/WP/DQ2_3") (pintype "passive"))
    )
    (net (code "189") (name "Net-(Y1-VDD)") (class "Default")
      (node (ref "C3") (pin "2") (pinfunction "2_2") (pintype "passive"))
      (node (ref "FB1") (pin "2") (pinfunction "2_2") (pintype "passive"))
      (node (ref "Y1") (pin "4") (pinfunction "VDD_4") (pintype "passive"))
    )
    (net (code "190") (name "Net-(Y2-VDD)") (class "Default")
      (node (ref "C5") (pin "2") (pinfunction "2_2") (pintype "passive"))
      (node (ref "FB2") (pin "2") (pinfunction "2_2") (pintype "passive"))
      (node (ref "Y2") (pin "4") (pinfunction "VDD_4") (pintype "passive"))
    )
    (net (code "191") (name "unconnected-(Y1-NC-Pad1)") (class "Default")
      (node (ref "Y1") (pin "1") (pinfunction "NC_1") (pintype "passive"))
    )
    (net (code "192") (name "unconnected-(Y2-NC-Pad1)") (class "Default")
      (node (ref "Y2") (pin "1") (pinfunction "NC_1") (pintype "passive"))
    )
  )
)
